# Peripherals_right.net
KiCad netlist of a schematic drawn in Altium Designer
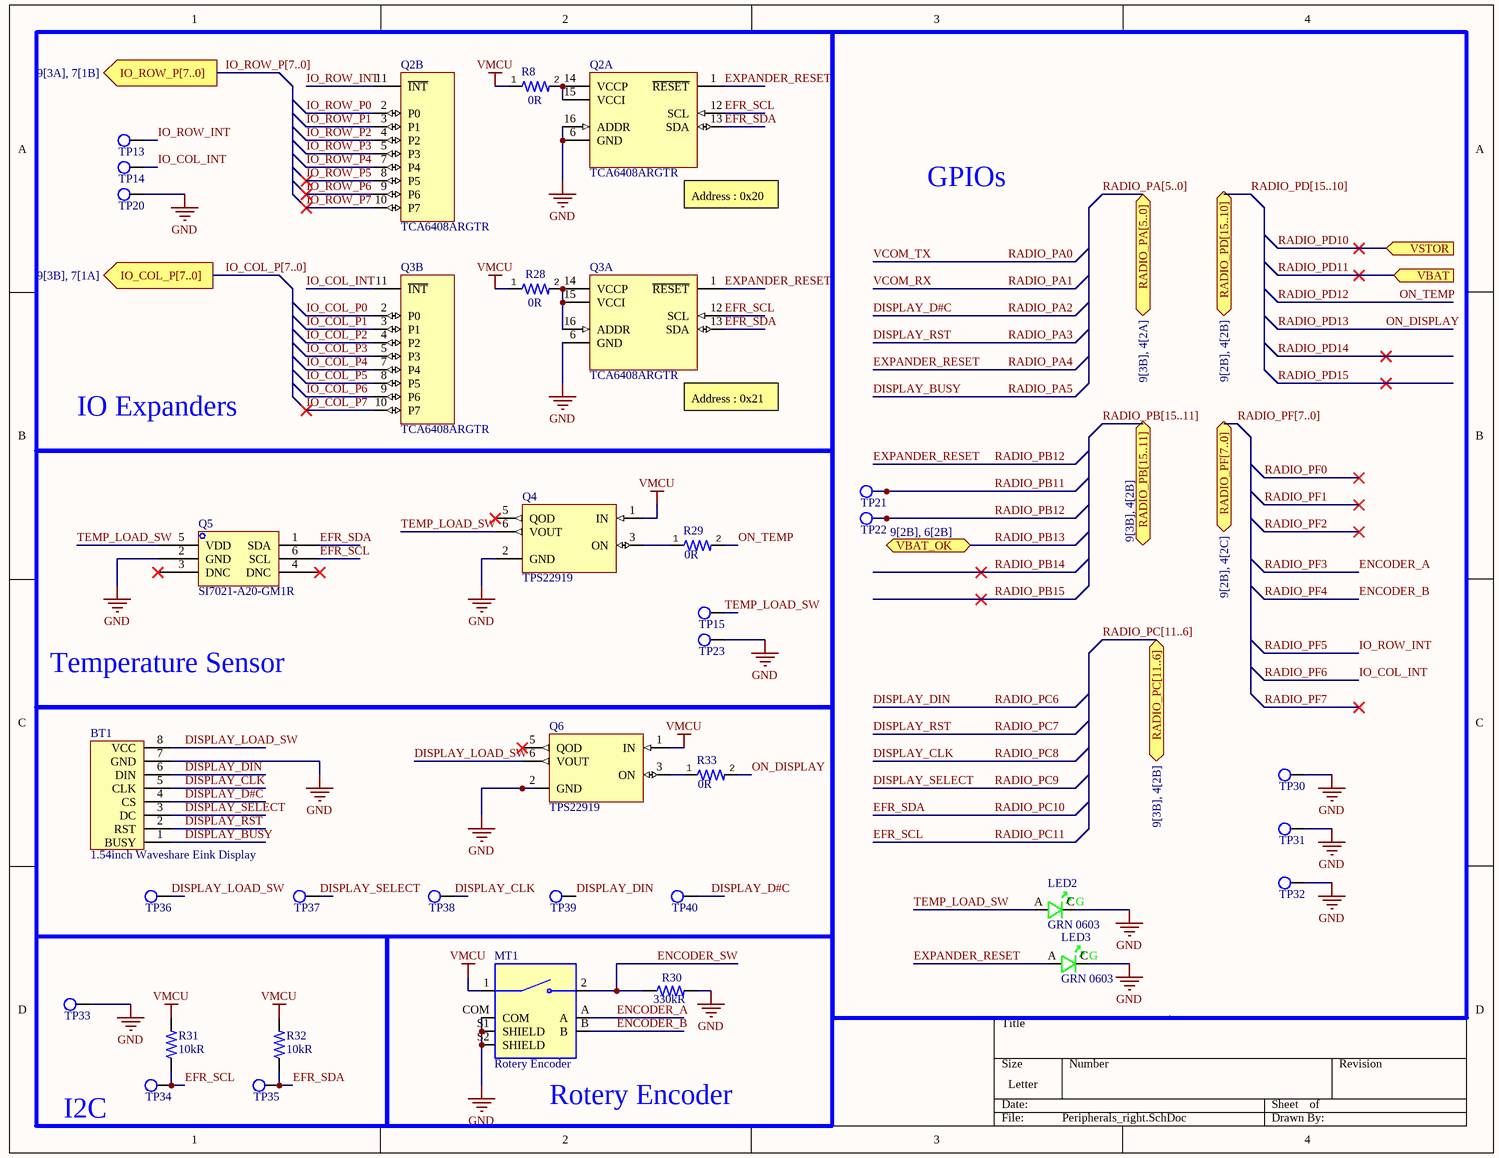
[diagram p0: Peripherals_right.SchDoc]

(export (version "E")
  (design (tool "Eeschema 10.0.6"))
  (components
    (comp (ref "BT1")
      (value "1.54inch Waveshare Eink Display")
      (footprint "1.54inch waveshare eink")
      (libsource (lib "Keyboard_parts") (part "1.54inch Waveshare Eink Display"))
    )
    (comp (ref "LED2")
      (value "GRN 0603")
      (footprint "LED 0603")
      (description "LED, 0603, GREEN, 430MCD, 520NM")
      (fields
        (field (name "MANUFACTURER") "Wurth Electronics")
        (field (name "MANUFACTURER PART NUMBER") "150060GS75000")
      )
      (libsource (lib "InsaneIntegratedLib") (part "LED Green 0603"))
    )
    (comp (ref "LED3")
      (value "GRN 0603")
      (footprint "LED 0603")
      (description "LED, 0603, GREEN, 430MCD, 520NM")
      (fields
        (field (name "MANUFACTURER") "Wurth Electronics")
        (field (name "MANUFACTURER PART NUMBER") "150060GS75000")
      )
      (libsource (lib "InsaneIntegratedLib") (part "LED Green 0603"))
    )
    (comp (ref "MT1")
      (value "Rotery Encoder")
      (footprint "Rotery Encoder")
      (description "Rotary Position Encoder, Single, 2 Channels")
      (fields (field (name "MP") "PEC11R-4215F-S0024") (field (name "MANUFACTURER") "Bourns"))
      (libsource (lib "InsaneIntegratedLib") (part "Rotery Encoder"))
    )
    (comp (ref "Q2")
      (value "TCA6408ARGTR")
      (footprint "TCA6408ARGTR - IO Expander")
      (description "Parallel I/O Port, 8-Bit, 8 I/O, CMOS, PQCC16")
      (fields (field (name "MANUFACTURER") "Texas Instruments"))
      (libsource (lib "Keyboard_parts") (part "TCA6408ARGTR"))
    )
    (comp (ref "Q3")
      (value "TCA6408ARGTR")
      (footprint "TCA6408ARGTR - IO Expander")
      (description "Parallel I/O Port, 8-Bit, 8 I/O, CMOS, PQCC16")
      (fields (field (name "MANUFACTURER") "Texas Instruments"))
      (libsource (lib "Keyboard_parts") (part "TCA6408ARGTR"))
    )
    (comp (ref "Q4")
      (value "TPS22919")
      (footprint "TPS22919DCKR - Load SW")
      (description "Buffer/Inverter Based Peripheral Driver, 3A, PDSO6")
      (fields
        (field (name "MANUFACTURER") "Texas Instruments")
        (field (name "MANUFACTURER PART NUMBER") "TPS22919DCKT")
      )
      (libsource (lib "Keyboard_parts") (part "TPS22919"))
    )
    (comp (ref "Q5")
      (value "SI7021-A20-GM1R")
      (footprint "Si7021-A20 - Temp")
      (description "Serial Switch/Digital Sensor, 14 Bit(s), 0.40Cel, Square, Surface Mount")
      (fields (field (name "MANUFACTURER") "Silicon Labs"))
      (libsource (lib "Keyboard_parts") (part "SI7021-A20-GM1R"))
    )
    (comp (ref "Q6")
      (value "TPS22919")
      (footprint "TPS22919DCKR - Load SW")
      (description "Buffer/Inverter Based Peripheral Driver, 3A, PDSO6")
      (fields
        (field (name "MANUFACTURER") "Texas Instruments")
        (field (name "MANUFACTURER PART NUMBER") "TPS22919DCKT")
      )
      (libsource (lib "Keyboard_parts") (part "TPS22919"))
    )
    (comp (ref "R8")
      (value "0R")
      (footprint "Resistor 0402")
      (description "Metal Glaze/thick Film, 0.0625W, 0ohm, Surface Mount, 0402")
      (fields
        (field (name "MANUFACTURER") "Yageo")
        (field (name "MANUFACTURER PART NUMBER") "RC0402JR-070RL")
      )
      (libsource (lib "InsaneIntegratedLib") (part "RES 0R 0402"))
    )
    (comp (ref "R28")
      (value "0R")
      (footprint "Resistor 0402")
      (description "Metal Glaze/thick Film, 0.0625W, 0ohm, Surface Mount, 0402")
      (fields
        (field (name "MANUFACTURER") "Yageo")
        (field (name "MANUFACTURER PART NUMBER") "RC0402JR-070RL")
      )
      (libsource (lib "InsaneIntegratedLib") (part "RES 0R 0402"))
    )
    (comp (ref "R29")
      (value "0R")
      (footprint "Resistor 0402")
      (description "Metal Glaze/thick Film, 0.0625W, 0ohm, Surface Mount, 0402")
      (fields
        (field (name "MANUFACTURER") "Yageo")
        (field (name "MANUFACTURER PART NUMBER") "RC0402JR-070RL")
      )
      (libsource (lib "InsaneIntegratedLib") (part "RES 0R 0402"))
    )
    (comp (ref "R30")
      (value "330kR")
      (footprint "Resistor 0603")
      (fields
        (field (name "MANUFACTURER") "Yageo")
        (field (name "MANUFACTURER PART NUMBER") "RC0603JR-07330KL")
        (field (name "TOLERANCE") "5%")
      )
      (libsource (lib "Keyboard_parts") (part "RES 330K 0603"))
    )
    (comp (ref "R31")
      (value "10kR")
      (footprint "Resistor 0603")
      (fields
        (field (name "MANUFACTURER") "Yageo")
        (field (name "MANUFACTURER PART NUMBER") "RC0603FR-0710KL")
        (field (name "TOLERANCE") "1%")
      )
      (libsource (lib "Keyboard_parts") (part "RES 10K 0603"))
    )
    (comp (ref "R32")
      (value "10kR")
      (footprint "Resistor 0603")
      (fields
        (field (name "MANUFACTURER") "Yageo")
        (field (name "MANUFACTURER PART NUMBER") "RC0603FR-0710KL")
        (field (name "TOLERANCE") "1%")
      )
      (libsource (lib "Keyboard_parts") (part "RES 10K 0603"))
    )
    (comp (ref "R33")
      (value "0R")
      (footprint "Resistor 0402")
      (description "Metal Glaze/thick Film, 0.0625W, 0ohm, Surface Mount, 0402")
      (fields
        (field (name "MANUFACTURER") "Yageo")
        (field (name "MANUFACTURER PART NUMBER") "RC0402JR-070RL")
      )
      (libsource (lib "InsaneIntegratedLib") (part "RES 0R 0402"))
    )
    (comp (ref "TP13")
      (value "Test point")
      (footprint "Test Point")
      (libsource (lib "Keyboard_parts") (part "Test point"))
    )
    (comp (ref "TP14")
      (value "Test point")
      (footprint "Test Point")
      (libsource (lib "Keyboard_parts") (part "Test point"))
    )
    (comp (ref "TP15")
      (value "Test point")
      (footprint "Test Point")
      (libsource (lib "Keyboard_parts") (part "Test point"))
    )
    (comp (ref "TP20")
      (value "Test point")
      (footprint "Test Point")
      (libsource (lib "Keyboard_parts") (part "Test point"))
    )
    (comp (ref "TP21")
      (value "Test point")
      (footprint "Test Point")
      (libsource (lib "Keyboard_parts") (part "Test point"))
    )
    (comp (ref "TP22")
      (value "Test point")
      (footprint "Test Point")
      (libsource (lib "Keyboard_parts") (part "Test point"))
    )
    (comp (ref "TP23")
      (value "Test point")
      (footprint "Test Point")
      (libsource (lib "Keyboard_parts") (part "Test point"))
    )
    (comp (ref "TP30")
      (value "Test point")
      (footprint "Test Point")
      (libsource (lib "Keyboard_parts") (part "Test point"))
    )
    (comp (ref "TP31")
      (value "Test point")
      (footprint "Test Point")
      (libsource (lib "Keyboard_parts") (part "Test point"))
    )
    (comp (ref "TP32")
      (value "Test point")
      (footprint "Test Point")
      (libsource (lib "Keyboard_parts") (part "Test point"))
    )
    (comp (ref "TP33")
      (value "Test point")
      (footprint "Test Point")
      (libsource (lib "Keyboard_parts") (part "Test point"))
    )
    (comp (ref "TP34")
      (value "Test point")
      (footprint "Test Point")
      (libsource (lib "Keyboard_parts") (part "Test point"))
    )
    (comp (ref "TP35")
      (value "Test point")
      (footprint "Test Point")
      (libsource (lib "Keyboard_parts") (part "Test point"))
    )
    (comp (ref "TP36")
      (value "Test point")
      (footprint "Test Point")
      (libsource (lib "Keyboard_parts") (part "Test point"))
    )
    (comp (ref "TP37")
      (value "Test point")
      (footprint "Test Point")
      (libsource (lib "Keyboard_parts") (part "Test point"))
    )
    (comp (ref "TP38")
      (value "Test point")
      (footprint "Test Point")
      (libsource (lib "Keyboard_parts") (part "Test point"))
    )
    (comp (ref "TP39")
      (value "Test point")
      (footprint "Test Point")
      (libsource (lib "Keyboard_parts") (part "Test point"))
    )
    (comp (ref "TP40")
      (value "Test point")
      (footprint "Test Point")
      (libsource (lib "Keyboard_parts") (part "Test point"))
    )
  )
  (nets
    (net (code "1") (name "/DISPLAY_LOAD_SW") (class "Default")
      (node (ref "BT1") (pin "8") (pinfunction "VCC_8") (pintype "passive"))
      (node (ref "Q6") (pin "6") (pinfunction "VOUT_6") (pintype "output"))
      (node (ref "TP36") (pin "1") (pinfunction "1_1") (pintype "passive"))
    )
    (net (code "2") (name "/ENCODER_SW") (class "Default")
      (node (ref "MT1") (pin "2") (pinfunction "2_2") (pintype "passive"))
      (node (ref "R30") (pin "1") (pinfunction "1_1") (pintype "passive"))
    )
    (net (code "3") (name "/IO_COL_P0") (class "Default")
      (node (ref "Q3") (pin "2") (pinfunction "P0_2") (pintype "bidirectional"))
    )
    (net (code "4") (name "/IO_COL_P1") (class "Default")
      (node (ref "Q3") (pin "3") (pinfunction "P1_3") (pintype "bidirectional"))
    )
    (net (code "5") (name "/IO_COL_P2") (class "Default")
      (node (ref "Q3") (pin "4") (pinfunction "P2_4") (pintype "bidirectional"))
    )
    (net (code "6") (name "/IO_COL_P3") (class "Default")
      (node (ref "Q3") (pin "5") (pinfunction "P3_5") (pintype "bidirectional"))
    )
    (net (code "7") (name "/IO_COL_P4") (class "Default")
      (node (ref "Q3") (pin "7") (pinfunction "P4_7") (pintype "bidirectional"))
    )
    (net (code "8") (name "/IO_COL_P5") (class "Default")
      (node (ref "Q3") (pin "8") (pinfunction "P5_8") (pintype "bidirectional"))
    )
    (net (code "9") (name "/IO_COL_P6") (class "Default")
      (node (ref "Q3") (pin "9") (pinfunction "P6_9") (pintype "bidirectional"))
    )
    (net (code "10") (name "/IO_COL_P7") (class "Default")
      (node (ref "Q3") (pin "10") (pinfunction "P7_10") (pintype "bidirectional+no_connect"))
    )
    (net (code "12") (name "/IO_ROW_P0") (class "Default")
      (node (ref "Q2") (pin "2") (pinfunction "P0_2") (pintype "bidirectional"))
    )
    (net (code "13") (name "/IO_ROW_P1") (class "Default")
      (node (ref "Q2") (pin "3") (pinfunction "P1_3") (pintype "bidirectional"))
    )
    (net (code "14") (name "/IO_ROW_P2") (class "Default")
      (node (ref "Q2") (pin "4") (pinfunction "P2_4") (pintype "bidirectional"))
    )
    (net (code "15") (name "/IO_ROW_P3") (class "Default")
      (node (ref "Q2") (pin "5") (pinfunction "P3_5") (pintype "bidirectional"))
    )
    (net (code "16") (name "/IO_ROW_P4") (class "Default")
      (node (ref "Q2") (pin "7") (pinfunction "P4_7") (pintype "bidirectional"))
    )
    (net (code "17") (name "/IO_ROW_P5") (class "Default")
      (node (ref "Q2") (pin "8") (pinfunction "P5_8") (pintype "bidirectional+no_connect"))
    )
    (net (code "18") (name "/IO_ROW_P6") (class "Default")
      (node (ref "Q2") (pin "9") (pinfunction "P6_9") (pintype "bidirectional+no_connect"))
    )
    (net (code "19") (name "/IO_ROW_P7") (class "Default")
      (node (ref "Q2") (pin "10") (pinfunction "P7_10") (pintype "bidirectional+no_connect"))
    )
    (net (code "23") (name "/RADIO_PA2") (class "Default")
      (node (ref "BT1") (pin "4") (pinfunction "CS_4") (pintype "passive"))
      (node (ref "TP40") (pin "1") (pinfunction "1_1") (pintype "passive"))
    )
    (net (code "24") (name "/RADIO_PA5") (class "Default")
      (node (ref "BT1") (pin "1") (pinfunction "BUSY_1") (pintype "passive"))
    )
    (net (code "26") (name "/RADIO_PB11") (class "Default")
      (node (ref "TP21") (pin "1") (pinfunction "1_1") (pintype "passive"))
    )
    (net (code "27") (name "/RADIO_PB12") (class "Default")
      (node (ref "LED3") (pin "A") (pinfunction "A_A") (pintype "passive"))
      (node (ref "Q2") (pin "1") (pinfunction "~{RESET}_1") (pintype "passive"))
      (node (ref "Q3") (pin "1") (pinfunction "~{RESET}_1") (pintype "passive"))
      (node (ref "TP22") (pin "1") (pinfunction "1_1") (pintype "passive"))
    )
    (net (code "32") (name "/RADIO_PC6") (class "Default")
      (node (ref "BT1") (pin "6") (pinfunction "DIN_6") (pintype "passive"))
      (node (ref "TP39") (pin "1") (pinfunction "1_1") (pintype "passive"))
    )
    (net (code "33") (name "/RADIO_PC7") (class "Default")
      (node (ref "BT1") (pin "2") (pinfunction "RST_2") (pintype "passive"))
    )
    (net (code "34") (name "/RADIO_PC8") (class "Default")
      (node (ref "BT1") (pin "5") (pinfunction "CLK_5") (pintype "passive"))
      (node (ref "TP38") (pin "1") (pinfunction "1_1") (pintype "passive"))
    )
    (net (code "35") (name "/RADIO_PC9") (class "Default")
      (node (ref "BT1") (pin "3") (pinfunction "DC_3") (pintype "passive"))
      (node (ref "TP37") (pin "1") (pinfunction "1_1") (pintype "passive"))
    )
    (net (code "36") (name "/RADIO_PC10") (class "Default")
      (node (ref "Q2") (pin "13") (pinfunction "SDA_13") (pintype "bidirectional"))
      (node (ref "Q3") (pin "13") (pinfunction "SDA_13") (pintype "bidirectional"))
      (node (ref "Q5") (pin "1") (pinfunction "SDA_1") (pintype "passive"))
      (node (ref "R32") (pin "1") (pinfunction "1_1") (pintype "passive"))
      (node (ref "TP35") (pin "1") (pinfunction "1_1") (pintype "passive"))
    )
    (net (code "37") (name "/RADIO_PC11") (class "Default")
      (node (ref "Q2") (pin "12") (pinfunction "SCL_12") (pintype "input"))
      (node (ref "Q3") (pin "12") (pinfunction "SCL_12") (pintype "input"))
      (node (ref "Q5") (pin "6") (pinfunction "SCL_6") (pintype "passive"))
      (node (ref "R31") (pin "1") (pinfunction "1_1") (pintype "passive"))
      (node (ref "TP34") (pin "1") (pinfunction "1_1") (pintype "passive"))
    )
    (net (code "41") (name "/RADIO_PD12") (class "Default")
      (node (ref "R29") (pin "2") (pinfunction "2_2") (pintype "passive"))
    )
    (net (code "42") (name "/RADIO_PD13") (class "Default")
      (node (ref "R33") (pin "2") (pinfunction "2_2") (pintype "passive"))
    )
    (net (code "49") (name "/RADIO_PF3") (class "Default")
      (node (ref "MT1") (pin "A") (pinfunction "A_A") (pintype "passive"))
    )
    (net (code "50") (name "/RADIO_PF4") (class "Default")
      (node (ref "MT1") (pin "B") (pinfunction "B_B") (pintype "passive"))
    )
    (net (code "51") (name "/RADIO_PF5") (class "Default")
      (node (ref "Q2") (pin "11") (pinfunction "~{INT}_11") (pintype "passive"))
      (node (ref "TP13") (pin "1") (pinfunction "1_1") (pintype "passive"))
    )
    (net (code "52") (name "/RADIO_PF6") (class "Default")
      (node (ref "Q3") (pin "11") (pinfunction "~{INT}_11") (pintype "passive"))
      (node (ref "TP14") (pin "1") (pinfunction "1_1") (pintype "passive"))
    )
    (net (code "55") (name "/TEMP_LOAD_SW") (class "Default")
      (node (ref "LED2") (pin "A") (pinfunction "A_A") (pintype "passive"))
      (node (ref "Q4") (pin "6") (pinfunction "VOUT_6") (pintype "output"))
      (node (ref "Q5") (pin "5") (pinfunction "VDD_5") (pintype "passive"))
      (node (ref "TP15") (pin "1") (pinfunction "1_1") (pintype "passive"))
    )
    (net (code "56") (name "GND") (class "Default")
      (node (ref "BT1") (pin "7") (pinfunction "GND_7") (pintype "passive"))
      (node (ref "LED2") (pin "C") (pinfunction "C_C") (pintype "passive"))
      (node (ref "LED3") (pin "C") (pinfunction "C_C") (pintype "passive"))
      (node (ref "MT1") (pin "COM") (pinfunction "COM_COM") (pintype "passive"))
      (node (ref "MT1") (pin "S1") (pinfunction "SHIELD_S1") (pintype "passive"))
      (node (ref "MT1") (pin "S2") (pinfunction "SHIELD_S2") (pintype "passive"))
      (node (ref "Q2") (pin "16") (pinfunction "ADDR_16") (pintype "input"))
      (node (ref "Q2") (pin "6") (pinfunction "GND_6") (pintype "passive"))
      (node (ref "Q3") (pin "6") (pinfunction "GND_6") (pintype "passive"))
      (node (ref "Q4") (pin "2") (pinfunction "GND_2") (pintype "passive"))
      (node (ref "Q5") (pin "2") (pinfunction "GND_2") (pintype "passive"))
      (node (ref "Q6") (pin "2") (pinfunction "GND_2") (pintype "passive"))
      (node (ref "R30") (pin "2") (pinfunction "2_2") (pintype "passive"))
      (node (ref "TP20") (pin "1") (pinfunction "1_1") (pintype "passive"))
      (node (ref "TP23") (pin "1") (pinfunction "1_1") (pintype "passive"))
      (node (ref "TP30") (pin "1") (pinfunction "1_1") (pintype "passive"))
      (node (ref "TP31") (pin "1") (pinfunction "1_1") (pintype "passive"))
      (node (ref "TP32") (pin "1") (pinfunction "1_1") (pintype "passive"))
      (node (ref "TP33") (pin "1") (pinfunction "1_1") (pintype "passive"))
    )
    (net (code "57") (name "Net-(Q2A-VCCI)") (class "Default")
      (node (ref "Q2") (pin "14") (pinfunction "VCCP_14") (pintype "power_in"))
      (node (ref "Q2") (pin "15") (pinfunction "VCCI_15") (pintype "power_in"))
      (node (ref "R8") (pin "2") (pinfunction "2_2") (pintype "passive"))
    )
    (net (code "58") (name "Net-(Q3A-ADDR)") (class "Default")
      (node (ref "Q3") (pin "14") (pinfunction "VCCP_14") (pintype "power_in"))
      (node (ref "Q3") (pin "15") (pinfunction "VCCI_15") (pintype "power_in"))
      (node (ref "Q3") (pin "16") (pinfunction "ADDR_16") (pintype "input"))
      (node (ref "R28") (pin "2") (pinfunction "2_2") (pintype "passive"))
    )
    (net (code "59") (name "Net-(Q4-ON)") (class "Default")
      (node (ref "Q4") (pin "3") (pinfunction "ON_3") (pintype "bidirectional"))
      (node (ref "R29") (pin "1") (pinfunction "1_1") (pintype "passive"))
    )
    (net (code "60") (name "Net-(Q6-ON)") (class "Default")
      (node (ref "Q6") (pin "3") (pinfunction "ON_3") (pintype "bidirectional"))
      (node (ref "R33") (pin "1") (pinfunction "1_1") (pintype "passive"))
    )
    (net (code "61") (name "VMCU") (class "Default")
      (node (ref "MT1") (pin "1") (pinfunction "1_1") (pintype "passive"))
      (node (ref "Q4") (pin "1") (pinfunction "IN_1") (pintype "input"))
      (node (ref "Q6") (pin "1") (pinfunction "IN_1") (pintype "input"))
      (node (ref "R28") (pin "1") (pinfunction "1_1") (pintype "passive"))
      (node (ref "R31") (pin "2") (pinfunction "2_2") (pintype "passive"))
      (node (ref "R32") (pin "2") (pinfunction "2_2") (pintype "passive"))
      (node (ref "R8") (pin "1") (pinfunction "1_1") (pintype "passive"))
    )
    (net (code "62") (name "unconnected-(Q4-QOD-Pad5)") (class "Default")
      (node (ref "Q4") (pin "5") (pinfunction "QOD_5") (pintype "output+no_connect"))
    )
    (net (code "63") (name "unconnected-(Q5-DNC-Pad3)") (class "Default")
      (node (ref "Q5") (pin "3") (pinfunction "DNC_3") (pintype "passive+no_connect"))
    )
    (net (code "64") (name "unconnected-(Q5-DNC-Pad4)") (class "Default")
      (node (ref "Q5") (pin "4") (pinfunction "DNC_4") (pintype "passive+no_connect"))
    )
    (net (code "65") (name "unconnected-(Q6-QOD-Pad5)") (class "Default")
      (node (ref "Q6") (pin "5") (pinfunction "QOD_5") (pintype "output+no_connect"))
    )
  )
)
